# UT-61E_BLB.net
KiCad netlist of a schematic drawn in EAGLE
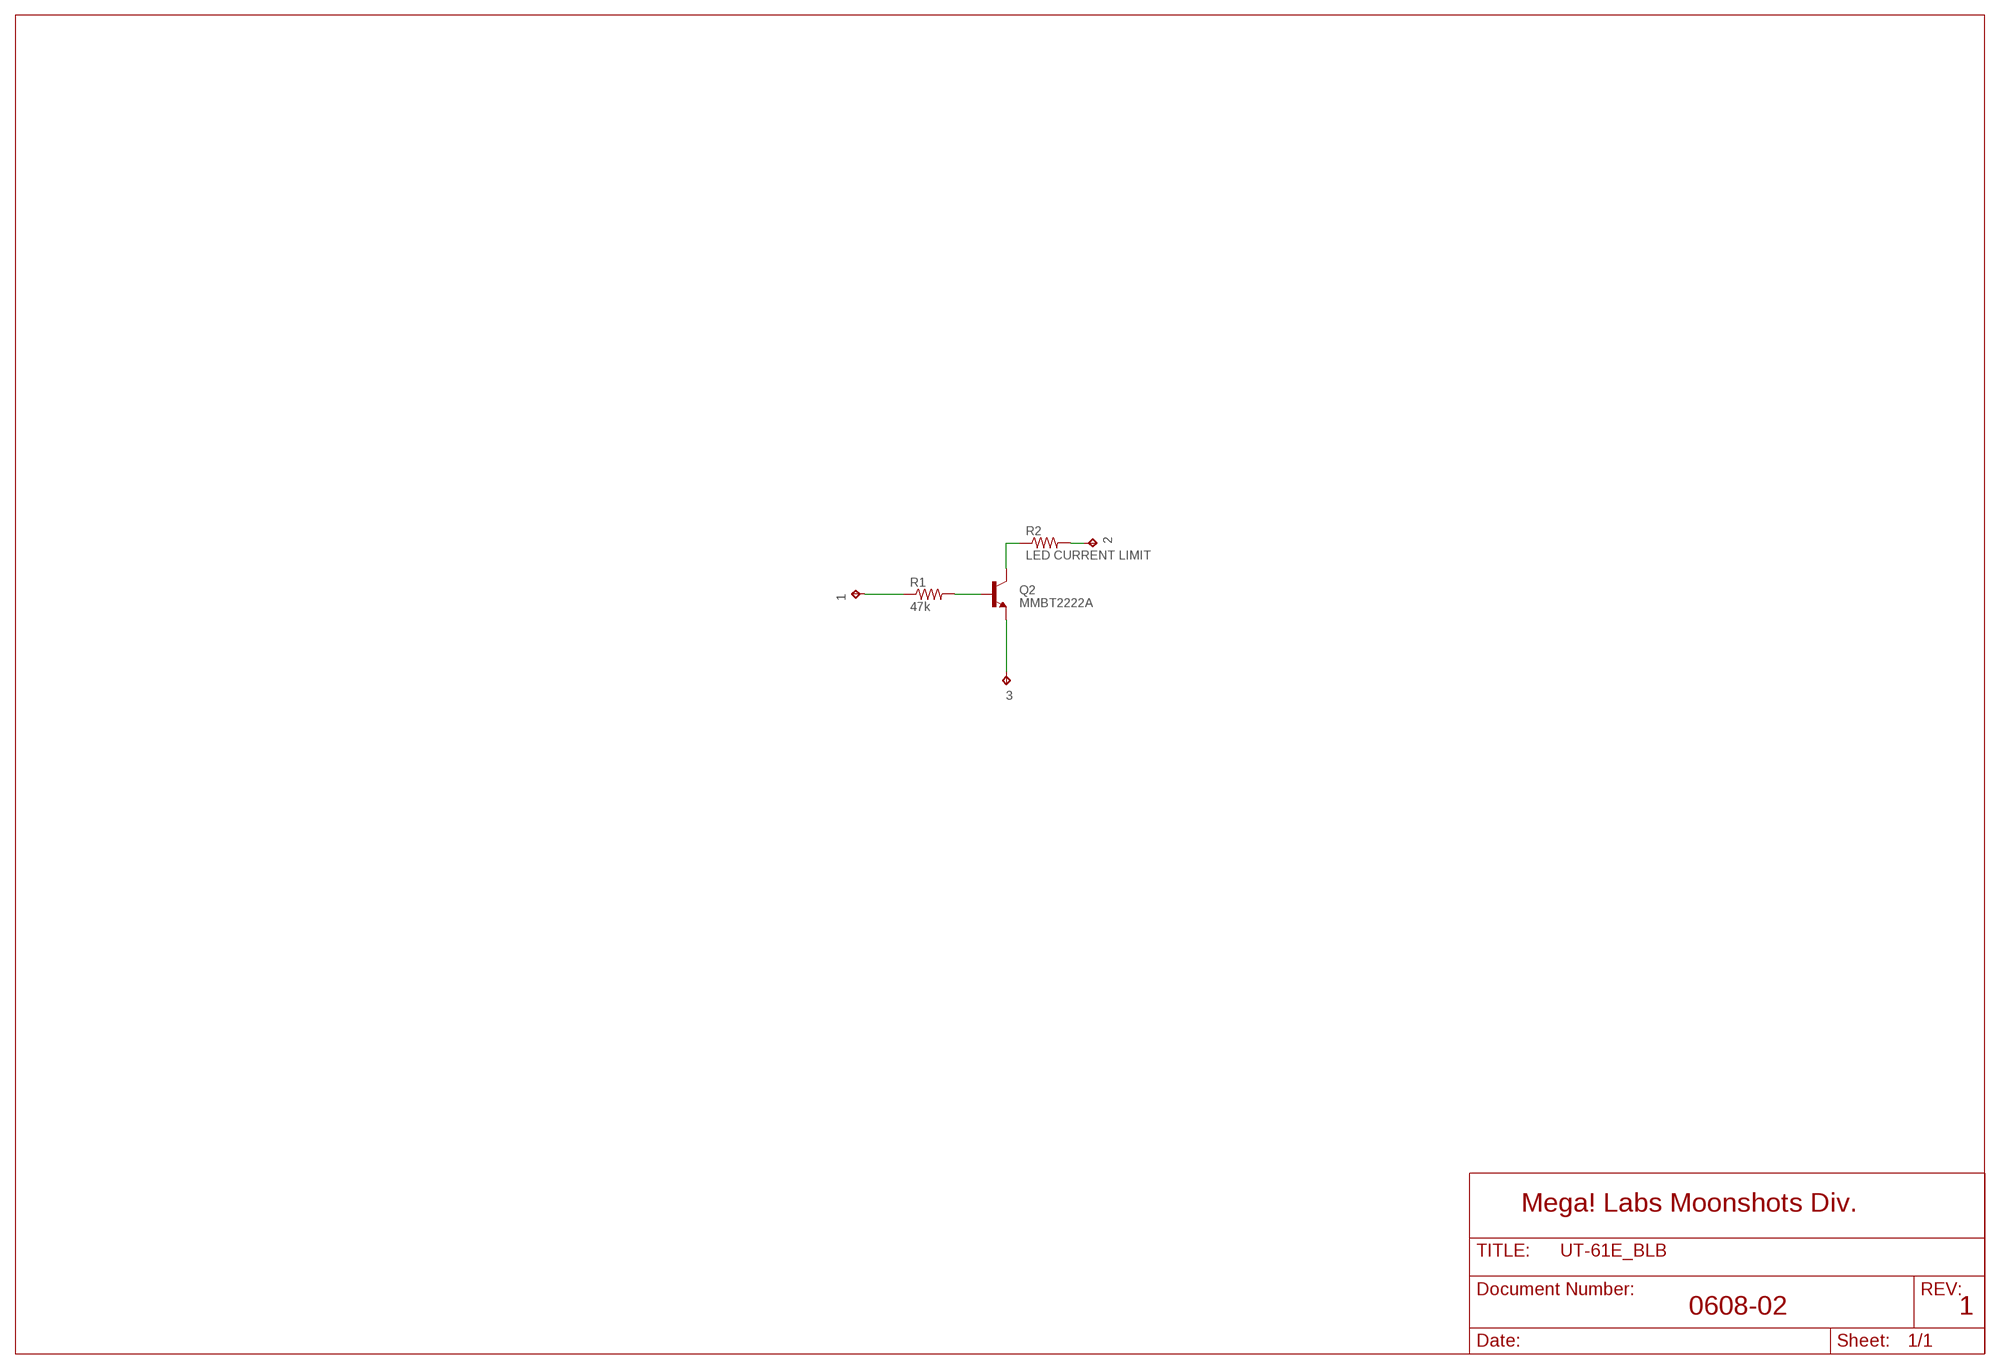
[diagram p0: schematic, sheet 1]

(export (version "E")
  (design (tool "Eeschema 10.0.6"))
  (components
    (comp (ref "1")
      (value "TPTP18SQ")
      (footprint "eagle-import:TP18SQ")
      (libsource (lib "eagle-import") (part "TPTP18SQ"))
    )
    (comp (ref "2")
      (value "TPTP18SQ")
      (footprint "eagle-import:TP18SQ")
      (libsource (lib "eagle-import") (part "TPTP18SQ"))
    )
    (comp (ref "3")
      (value "TPTP18SQ")
      (footprint "eagle-import:TP18SQ")
      (libsource (lib "eagle-import") (part "TPTP18SQ"))
    )
    (comp (ref "Q2")
      (value "MMBT2222A")
      (footprint "eagle-import:SOT23-3")
      (libsource (lib "eagle-import") (part "TRANSISTOR_NPNMMBT2222A"))
    )
    (comp (ref "R1")
      (value "47k")
      (footprint "eagle-import:0805")
      (libsource (lib "eagle-import") (part "RESISTOR0805-RES"))
    )
    (comp (ref "R2")
      (value "LED CURRENT LIMIT")
      (footprint "eagle-import:0805")
      (libsource (lib "eagle-import") (part "RESISTOR0805-RES"))
    )
  )
  (nets
    (net (code "1") (name "Net-(1-PadTP)") (class "Default")
      (node (ref "1") (pin "TP") (pinfunction "TP_TP") (pintype "input"))
      (node (ref "R1") (pin "1") (pinfunction "1_1") (pintype "passive"))
    )
    (net (code "2") (name "Net-(2-PadTP)") (class "Default")
      (node (ref "2") (pin "TP") (pinfunction "TP_TP") (pintype "input"))
      (node (ref "R2") (pin "2") (pinfunction "2_2") (pintype "passive"))
    )
    (net (code "3") (name "Net-(Q2-B)") (class "Default")
      (node (ref "Q2") (pin "1") (pinfunction "B_1") (pintype "passive"))
      (node (ref "R1") (pin "2") (pinfunction "2_2") (pintype "passive"))
    )
    (net (code "4") (name "Net-(Q2-C)") (class "Default")
      (node (ref "Q2") (pin "3") (pinfunction "C_3") (pintype "passive"))
      (node (ref "R2") (pin "1") (pinfunction "1_1") (pintype "passive"))
    )
    (net (code "5") (name "Net-(Q2-E)") (class "Default")
      (node (ref "3") (pin "TP") (pinfunction "TP_TP") (pintype "input"))
      (node (ref "Q2") (pin "2") (pinfunction "E_2") (pintype "passive"))
    )
  )
)
